# digAudio-OC0808.net
KiCad netlist of a schematic drawn in EAGLE
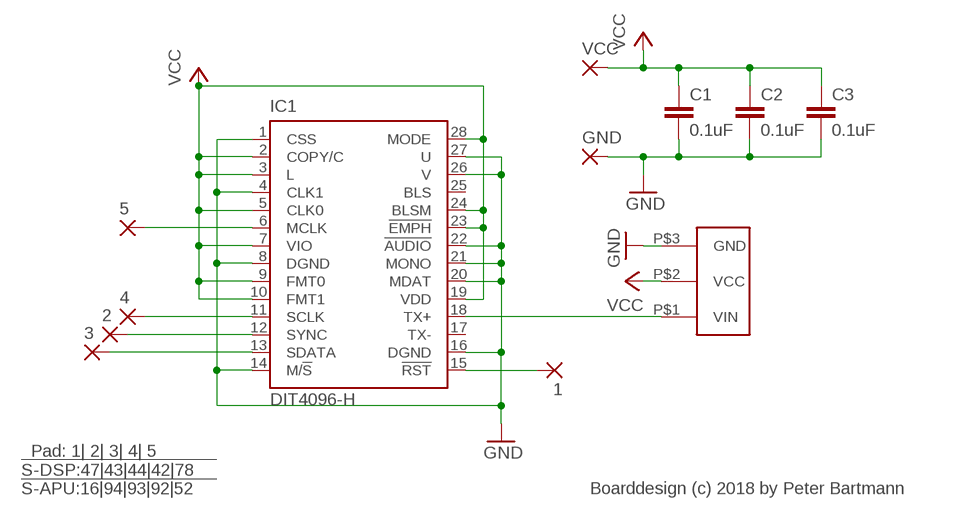
[diagram p0: schematic, sheet 1]

(export (version "E")
  (design (tool "Eeschema 10.0.6"))
  (components
    (comp (ref "1")
      (value "SMD1")
      (footprint "eagle-import:SMD0,8-1,6")
      (libsource (lib "eagle-import") (part "SMD1"))
    )
    (comp (ref "2")
      (value "SMD1")
      (footprint "eagle-import:SMD0,8-1,6")
      (libsource (lib "eagle-import") (part "SMD1"))
    )
    (comp (ref "3")
      (value "SMD1")
      (footprint "eagle-import:SMD0,8-1,6")
      (libsource (lib "eagle-import") (part "SMD1"))
    )
    (comp (ref "4")
      (value "SMD1")
      (footprint "eagle-import:SMD0,8-1,6")
      (libsource (lib "eagle-import") (part "SMD1"))
    )
    (comp (ref "5")
      (value "SMD1")
      (footprint "eagle-import:SMD0,8-1,6")
      (libsource (lib "eagle-import") (part "SMD1"))
    )
    (comp (ref "C1")
      (value "0.1uF")
      (footprint "eagle-import:C0603")
      (libsource (lib "eagle-import") (part "C-EUC0603"))
    )
    (comp (ref "C2")
      (value "0.1uF")
      (footprint "eagle-import:C0603")
      (libsource (lib "eagle-import") (part "C-EUC0603"))
    )
    (comp (ref "C3")
      (value "0.1uF")
      (footprint "eagle-import:C0603")
      (libsource (lib "eagle-import") (part "C-EUC0603"))
    )
    (comp (ref "GND")
      (value "SMD2")
      (footprint "eagle-import:SMD1,27-2,54")
      (libsource (lib "eagle-import") (part "SMD2"))
    )
    (comp (ref "IC1")
      (value "DIT4096-H")
      (footprint "eagle-import:PW_R-PDSO-G28")
      (fields (field (name "MF") "TEXAS INSTRUMENTS") (field (name "MPN") "DIT4192IPW"))
      (libsource (lib "eagle-import") (part "DIT4192-H"))
    )
    (comp (ref "U$1")
      (value "JT_OC0808")
      (footprint "eagle-import:JT_OC-0808T_008")
      (libsource (lib "eagle-import") (part "JT_OC0808"))
    )
    (comp (ref "VCC")
      (value "SMD2")
      (footprint "eagle-import:SMD1,27-2,54")
      (libsource (lib "eagle-import") (part "SMD2"))
    )
  )
  (nets
    (net (code "1") (name "GND") (class "Default")
      (node (ref "C1") (pin "2") (pinfunction "2_2") (pintype "passive"))
      (node (ref "C2") (pin "2") (pinfunction "2_2") (pintype "passive"))
      (node (ref "C3") (pin "2") (pinfunction "2_2") (pintype "passive"))
      (node (ref "GND") (pin "1") (pinfunction "P_1") (pintype "passive"))
      (node (ref "IC1") (pin "1") (pinfunction "CSS_1") (pintype "input"))
      (node (ref "IC1") (pin "14") (pinfunction "M/~{S}_14") (pintype "input"))
      (node (ref "IC1") (pin "16") (pinfunction "DGND_16") (pintype "power_in"))
      (node (ref "IC1") (pin "20") (pinfunction "MDAT_20") (pintype "input"))
      (node (ref "IC1") (pin "21") (pinfunction "MONO_21") (pintype "input"))
      (node (ref "IC1") (pin "22") (pinfunction "~{AUDIO}_22") (pintype "input"))
      (node (ref "IC1") (pin "26") (pinfunction "V_26") (pintype "input"))
      (node (ref "IC1") (pin "27") (pinfunction "U_27") (pintype "input"))
      (node (ref "IC1") (pin "4") (pinfunction "CLK1_4") (pintype "input"))
      (node (ref "IC1") (pin "8") (pinfunction "DGND_8") (pintype "power_in"))
      (node (ref "U$1") (pin "P$3") (pinfunction "GND_P$3") (pintype "bidirectional"))
    )
    (net (code "2") (name "Net-(1-P)") (class "Default")
      (node (ref "1") (pin "P$1") (pinfunction "P_P$1") (pintype "passive"))
      (node (ref "IC1") (pin "15") (pinfunction "~{RST}_15") (pintype "input"))
    )
    (net (code "3") (name "Net-(2-P)") (class "Default")
      (node (ref "2") (pin "P$1") (pinfunction "P_P$1") (pintype "passive"))
      (node (ref "IC1") (pin "12") (pinfunction "SYNC_12") (pintype "bidirectional"))
    )
    (net (code "4") (name "Net-(3-P)") (class "Default")
      (node (ref "3") (pin "P$1") (pinfunction "P_P$1") (pintype "passive"))
      (node (ref "IC1") (pin "13") (pinfunction "SDATA_13") (pintype "input"))
    )
    (net (code "5") (name "Net-(4-P)") (class "Default")
      (node (ref "4") (pin "P$1") (pinfunction "P_P$1") (pintype "passive"))
      (node (ref "IC1") (pin "11") (pinfunction "SCLK_11") (pintype "bidirectional"))
    )
    (net (code "6") (name "Net-(5-P)") (class "Default")
      (node (ref "5") (pin "P$1") (pinfunction "P_P$1") (pintype "passive"))
      (node (ref "IC1") (pin "6") (pinfunction "MCLK_6") (pintype "input"))
    )
    (net (code "7") (name "Net-(IC1-TX+)") (class "Default")
      (node (ref "IC1") (pin "18") (pinfunction "TX+_18") (pintype "output"))
      (node (ref "U$1") (pin "P$1") (pinfunction "VIN_P$1") (pintype "bidirectional"))
    )
    (net (code "8") (name "VCC") (class "Default")
      (node (ref "C1") (pin "1") (pinfunction "1_1") (pintype "passive"))
      (node (ref "C2") (pin "1") (pinfunction "1_1") (pintype "passive"))
      (node (ref "C3") (pin "1") (pinfunction "1_1") (pintype "passive"))
      (node (ref "IC1") (pin "10") (pinfunction "FMT1_10") (pintype "input"))
      (node (ref "IC1") (pin "19") (pinfunction "VDD_19") (pintype "power_in"))
      (node (ref "IC1") (pin "2") (pinfunction "COPY/C_2") (pintype "input"))
      (node (ref "IC1") (pin "23") (pinfunction "~{EMPH}_23") (pintype "input"))
      (node (ref "IC1") (pin "24") (pinfunction "BLSM_24") (pintype "input"))
      (node (ref "IC1") (pin "28") (pinfunction "MODE_28") (pintype "input"))
      (node (ref "IC1") (pin "3") (pinfunction "L_3") (pintype "input"))
      (node (ref "IC1") (pin "5") (pinfunction "CLK0_5") (pintype "input"))
      (node (ref "IC1") (pin "7") (pinfunction "VIO_7") (pintype "power_in"))
      (node (ref "IC1") (pin "9") (pinfunction "FMT0_9") (pintype "input"))
      (node (ref "U$1") (pin "P$2") (pinfunction "VCC_P$2") (pintype "bidirectional"))
      (node (ref "VCC") (pin "1") (pinfunction "P_1") (pintype "passive"))
    )
    (net (code "9") (name "unconnected-(IC1-BLS-Pad25)") (class "Default")
      (node (ref "IC1") (pin "25") (pinfunction "BLS_25") (pintype "bidirectional"))
    )
    (net (code "10") (name "unconnected-(IC1-TX--Pad17)") (class "Default")
      (node (ref "IC1") (pin "17") (pinfunction "TX-_17") (pintype "output"))
    )
  )
)
